# logi-cmos-7725-7670-NoFFC.net
KiCad netlist of a schematic drawn in Altium Designer
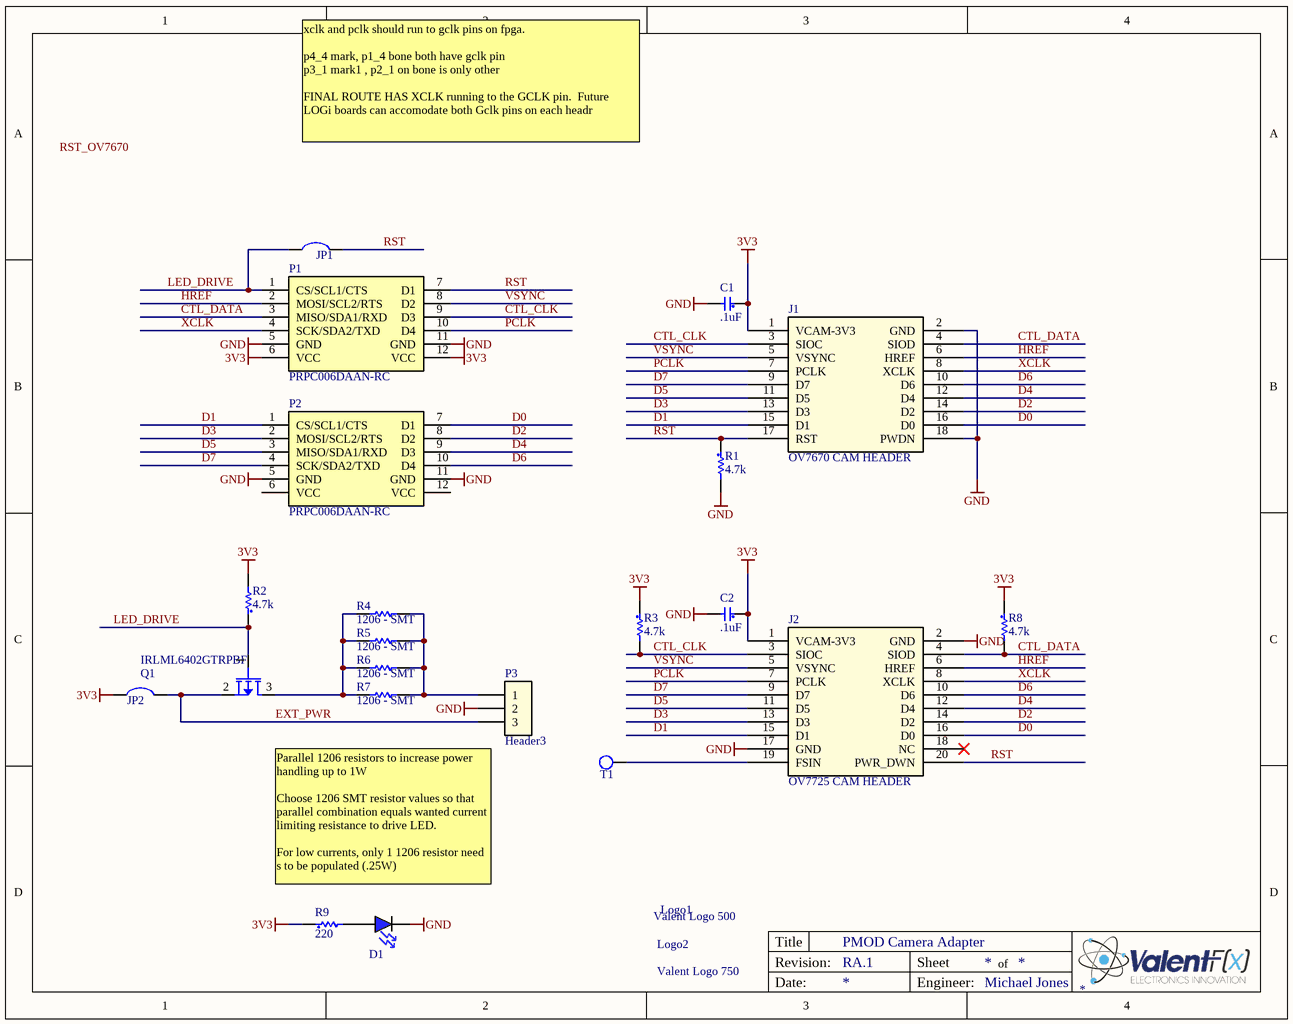
[diagram p0: logi-cmos-7725-7670-NoFFC.SchDoc]

(export (version "E")
  (design (tool "Eeschema 10.0.6"))
  (components
    (comp (ref "C1")
      (value ".1uF")
      (footprint "mRCL:C0603")
      (description ".10uF X7R 20% (MLCC) - SMD/SMT 0603 25volts")
      (fields (field (name "MANUFACTURER") "TDK") (field (name "MANUFACTURER PART NUMBER") "C1608X7R1E104MT"))
      (libsource (lib "mCapacitors") (part "C0603 - C1608X7R1E104MT"))
    )
    (comp (ref "C2")
      (value ".1uF")
      (footprint "mRCL:C0603")
      (description ".10uF X7R 20% (MLCC) - SMD/SMT 0603 25volts")
      (fields (field (name "MANUFACTURER") "TDK") (field (name "MANUFACTURER PART NUMBER") "C1608X7R1E104MT"))
      (libsource (lib "mCapacitors") (part "C0603 - C1608X7R1E104MT"))
    )
    (comp (ref "D1")
      (value "BLUE LED0603")
      (footprint "LED_0603 - BLUE")
      (description "BLUE Standard LED - SMD Blue 470nm 40mcd 20mA")
      (fields
        (field (name "MANUFACTURER") "Harvatek International")
        (field (name "MANUFACTURER PART NUMBER") "HT-193NB-5589")
      )
      (libsource (lib "mDiode") (part "LED0603 - HT-193NB-5589"))
    )
    (comp (ref "J1")
      (value "OV7670 CAM HEADER")
      (footprint "HEADER_9x2_40_100 1-3-5 THRU DIP")
      (description "CMOS CAMERA HEADER")
      (fields
        (field (name "MANUFACTURER") "Sullins Connector Solutions")
        (field (name "MANUFACTURER PART NUMBER") "PPPC092LFBN-RC")
      )
      (libsource (lib "mModule") (part "CAM - OV7670"))
    )
    (comp (ref "J2")
      (value "OV7725 CAM HEADER")
      (footprint "HEADER_10x2_40_100 1-3-5 THRU DIP")
      (description "CMOS CAMERA HEADER")
      (fields
        (field (name "MANUFACTURER") "Sullins Connector Solutions")
        (field (name "MANUFACTURER PART NUMBER") "SFH11-PBPC-D10-ST-BK")
      )
      (libsource (lib "mModule") (part "CAM - 0V7725"))
    )
    (comp (ref "JP1")
      (value "Solder Jumper")
      (footprint "SOLDER_JUMPER")
      (description "Solder/Configuration Jumper")
      (fields (field (name "MANUFACTURER") "n/a"))
      (libsource (lib "mConnector") (part "Solder Jumper"))
    )
    (comp (ref "JP2")
      (value "Solder Jumper")
      (footprint "SOLDER_JUMPER")
      (description "Solder/Configuration Jumper")
      (fields (field (name "MANUFACTURER") "n/a"))
      (libsource (lib "mConnector") (part "Solder Jumper"))
    )
    (comp (ref "Logo1")
      (value "Valent Logo 500")
      (footprint "VALENTFX_500-SolderMask")
      (libsource (lib "mLogos") (part "Valent Logo 500"))
    )
    (comp (ref "Logo2")
      (value "Valent Logo 750")
      (footprint "VALENTFX_750-SolderMask-BOT")
      (libsource (lib "mLogos") (part "Valent Logo 750"))
    )
    (comp (ref "P1")
      (value "PRPC006DAAN-RC")
      (footprint "mconnector:PMOD HEADER - Male")
      (fields
        (field (name "MANUFACTURER") "Samtec")
        (field (name "MANUFACTURER PART NUMBER") "MTSW-106-07-G-D-130-RA")
      )
      (libsource (lib "mConnector") (part "PRPC006DAAN-RC"))
    )
    (comp (ref "P2")
      (value "PRPC006DAAN-RC")
      (footprint "mconnector:PMOD HEADER - Male")
      (fields
        (field (name "MANUFACTURER") "Samtec")
        (field (name "MANUFACTURER PART NUMBER") "MTSW-106-07-G-D-130-RA")
      )
      (libsource (lib "mConnector") (part "PRPC006DAAN-RC"))
    )
    (comp (ref "P3")
      (value "Header3")
      (footprint "HEADER_3_40_100 THRU SIP")
      (description "Header  pin")
      (libsource (lib "mConnector") (part "Header3"))
    )
    (comp (ref "Q1")
      (value "IRLML6402GTRPBF")
      (footprint "SOT-23")
      (description "MOSFET P-CH 20V 3.7A SOT-23-3")
      (fields (field (name "MANUFACTURER") "International Rectifier"))
      (libsource (lib "mTransistor") (part "PMOS - IRLML6402GTRPBF"))
    )
    (comp (ref "R1")
      (value "4.7k")
      (footprint "mRCL:R0603")
      (description "4.7k Thick Film Resistors - SMD 1/10watt 4.7Kohms 1%")
      (fields
        (field (name "MANUFACTURER") "Vishay Dale")
        (field (name "MANUFACTURER PART NUMBER") "CRCW06034K70FKEA")
      )
      (libsource (lib "mResistors") (part "R0603 - CRCW06034K70FKEA"))
    )
    (comp (ref "R2")
      (value "4.7k")
      (footprint "mRCL:R0603")
      (description "4.7k Thick Film Resistors - SMD 1/10watt 4.7Kohms 1%")
      (fields
        (field (name "MANUFACTURER") "Vishay Dale")
        (field (name "MANUFACTURER PART NUMBER") "CRCW06034K70FKEA")
      )
      (libsource (lib "mResistors") (part "R0603 - CRCW06034K70FKEA"))
    )
    (comp (ref "R3")
      (value "4.7k")
      (footprint "mRCL:R0603")
      (description "4.7k Thick Film Resistors - SMD 1/10watt 4.7Kohms 1%")
      (fields
        (field (name "MANUFACTURER") "Vishay Dale")
        (field (name "MANUFACTURER PART NUMBER") "CRCW06034K70FKEA")
      )
      (libsource (lib "mResistors") (part "R0603 - CRCW06034K70FKEA"))
    )
    (comp (ref "R4")
      (value "1206 - SMT")
      (footprint "R1206")
      (description "RES 270 OHM 1/4W 5% 1206 SMD")
      (fields
        (field (name "MANUFACTURER") "Panasonic - ECG")
        (field (name "MANUFACTURER PART NUMBER") "ERJ-8GEYJ271V")
      )
      (libsource (lib "eResistors") (part "ERJ-8GEYJ271V"))
    )
    (comp (ref "R5")
      (value "1206 - SMT")
      (footprint "R1206")
      (description "RES 270 OHM 1/4W 5% 1206 SMD")
      (fields
        (field (name "MANUFACTURER") "Panasonic - ECG")
        (field (name "MANUFACTURER PART NUMBER") "ERJ-8GEYJ271V")
      )
      (libsource (lib "eResistors") (part "ERJ-8GEYJ271V"))
    )
    (comp (ref "R6")
      (value "1206 - SMT")
      (footprint "R1206")
      (description "RES 270 OHM 1/4W 5% 1206 SMD")
      (fields
        (field (name "MANUFACTURER") "Panasonic - ECG")
        (field (name "MANUFACTURER PART NUMBER") "ERJ-8GEYJ271V")
      )
      (libsource (lib "eResistors") (part "ERJ-8GEYJ271V"))
    )
    (comp (ref "R7")
      (value "1206 - SMT")
      (footprint "R1206")
      (description "RES 270 OHM 1/4W 5% 1206 SMD")
      (fields
        (field (name "MANUFACTURER") "Panasonic - ECG")
        (field (name "MANUFACTURER PART NUMBER") "ERJ-8GEYJ271V")
      )
      (libsource (lib "eResistors") (part "ERJ-8GEYJ271V"))
    )
    (comp (ref "R8")
      (value "4.7k")
      (footprint "mRCL:R0603")
      (description "4.7k Thick Film Resistors - SMD 1/10watt 4.7Kohms 1%")
      (fields
        (field (name "MANUFACTURER") "Vishay Dale")
        (field (name "MANUFACTURER PART NUMBER") "CRCW06034K70FKEA")
      )
      (libsource (lib "mResistors") (part "R0603 - CRCW06034K70FKEA"))
    )
    (comp (ref "R9")
      (value "220")
      (footprint "mRCL:R0603")
      (description "220 - thick Film Resistors - SMD 0603 220ohms 1% Tol")
      (fields
        (field (name "MANUFACTURER") "Panasonic - ECG")
        (field (name "MANUFACTURER PART NUMBER") "ERJ-3EKF2200V")
      )
      (libsource (lib "mResistors") (part "R0603 - ERJ-3EKF2200V"))
    )
    (comp (ref "T1")
      (value "Test Point")
      (footprint "Tp 25-40")
      (description "Test Point Smaller Symbol")
      (libsource (lib "mConnector") (part "Test Point 2"))
    )
  )
  (nets
    (net (code "1") (name "/CTL_CLK") (class "Default")
      (node (ref "J1") (pin "3") (pinfunction "SIOC_3") (pintype "passive"))
      (node (ref "J2") (pin "3") (pinfunction "SIOC_3") (pintype "passive"))
      (node (ref "P1") (pin "9") (pinfunction "D3_9") (pintype "power_in"))
      (node (ref "R3") (pin "2") (pinfunction "2_2") (pintype "passive"))
    )
    (net (code "2") (name "/CTL_DATA") (class "Default")
      (node (ref "J1") (pin "4") (pinfunction "SIOD_4") (pintype "passive"))
      (node (ref "J2") (pin "4") (pinfunction "SIOD_4") (pintype "passive"))
      (node (ref "P1") (pin "3") (pinfunction "MISO/SDA1/RXD_3") (pintype "power_in"))
      (node (ref "R8") (pin "2") (pinfunction "2_2") (pintype "passive"))
    )
    (net (code "3") (name "/D0") (class "Default")
      (node (ref "J1") (pin "16") (pinfunction "D0_16") (pintype "passive"))
      (node (ref "J2") (pin "16") (pinfunction "D0_16") (pintype "passive"))
      (node (ref "P2") (pin "7") (pinfunction "D1_7") (pintype "power_in"))
    )
    (net (code "4") (name "/D1") (class "Default")
      (node (ref "J1") (pin "15") (pinfunction "D1_15") (pintype "passive"))
      (node (ref "J2") (pin "15") (pinfunction "D1_15") (pintype "passive"))
      (node (ref "P2") (pin "1") (pinfunction "CS/SCL1/CTS_1") (pintype "power_in"))
    )
    (net (code "5") (name "/D2") (class "Default")
      (node (ref "J1") (pin "14") (pinfunction "D2_14") (pintype "passive"))
      (node (ref "J2") (pin "14") (pinfunction "D2_14") (pintype "passive"))
      (node (ref "P2") (pin "8") (pinfunction "D2_8") (pintype "power_in"))
    )
    (net (code "6") (name "/D3") (class "Default")
      (node (ref "J1") (pin "13") (pinfunction "D3_13") (pintype "passive"))
      (node (ref "J2") (pin "13") (pinfunction "D3_13") (pintype "passive"))
      (node (ref "P2") (pin "2") (pinfunction "MOSI/SCL2/RTS_2") (pintype "power_in"))
    )
    (net (code "7") (name "/D4") (class "Default")
      (node (ref "J1") (pin "12") (pinfunction "D4_12") (pintype "passive"))
      (node (ref "J2") (pin "12") (pinfunction "D4_12") (pintype "passive"))
      (node (ref "P2") (pin "9") (pinfunction "D3_9") (pintype "power_in"))
    )
    (net (code "8") (name "/D5") (class "Default")
      (node (ref "J1") (pin "11") (pinfunction "D5_11") (pintype "passive"))
      (node (ref "J2") (pin "11") (pinfunction "D5_11") (pintype "passive"))
      (node (ref "P2") (pin "3") (pinfunction "MISO/SDA1/RXD_3") (pintype "power_in"))
    )
    (net (code "9") (name "/D6") (class "Default")
      (node (ref "J1") (pin "10") (pinfunction "D6_10") (pintype "passive"))
      (node (ref "J2") (pin "10") (pinfunction "D6_10") (pintype "passive"))
      (node (ref "P2") (pin "10") (pinfunction "D4_10") (pintype "power_in"))
    )
    (net (code "10") (name "/D7") (class "Default")
      (node (ref "J1") (pin "9") (pinfunction "D7_9") (pintype "passive"))
      (node (ref "J2") (pin "9") (pinfunction "D7_9") (pintype "passive"))
      (node (ref "P2") (pin "4") (pinfunction "SCK/SDA2/TXD_4") (pintype "power_in"))
    )
    (net (code "11") (name "/EXT_PWR") (class "Default")
      (node (ref "JP2") (pin "2") (pinfunction "2_2") (pintype "passive"))
      (node (ref "P3") (pin "3") (pinfunction "3_3") (pintype "passive"))
      (node (ref "Q1") (pin "2") (pinfunction "S_2") (pintype "passive"))
    )
    (net (code "12") (name "/HREF") (class "Default")
      (node (ref "J1") (pin "6") (pinfunction "HREF_6") (pintype "passive"))
      (node (ref "J2") (pin "6") (pinfunction "HREF_6") (pintype "passive"))
      (node (ref "P1") (pin "2") (pinfunction "MOSI/SCL2/RTS_2") (pintype "power_in"))
    )
    (net (code "13") (name "/LED_DRIVE") (class "Default")
      (node (ref "JP1") (pin "1") (pinfunction "1_1") (pintype "passive"))
      (node (ref "P1") (pin "1") (pinfunction "CS/SCL1/CTS_1") (pintype "power_in"))
      (node (ref "Q1") (pin "1") (pinfunction "G_1") (pintype "passive"))
      (node (ref "R2") (pin "1") (pinfunction "1_1") (pintype "passive"))
    )
    (net (code "14") (name "/PCLK") (class "Default")
      (node (ref "J1") (pin "7") (pinfunction "PCLK_7") (pintype "passive"))
      (node (ref "J2") (pin "7") (pinfunction "PCLK_7") (pintype "passive"))
      (node (ref "P1") (pin "10") (pinfunction "D4_10") (pintype "power_in"))
    )
    (net (code "15") (name "/RST") (class "Default")
      (node (ref "J1") (pin "17") (pinfunction "RST_17") (pintype "passive"))
      (node (ref "J2") (pin "20") (pinfunction "PWR_DWN_20") (pintype "passive"))
      (node (ref "JP1") (pin "2") (pinfunction "2_2") (pintype "passive"))
      (node (ref "P1") (pin "7") (pinfunction "D1_7") (pintype "power_in"))
      (node (ref "R1") (pin "1") (pinfunction "1_1") (pintype "passive"))
    )
    (net (code "17") (name "/VSYNC") (class "Default")
      (node (ref "J1") (pin "5") (pinfunction "VSYNC_5") (pintype "passive"))
      (node (ref "J2") (pin "5") (pinfunction "VSYNC_5") (pintype "passive"))
      (node (ref "P1") (pin "8") (pinfunction "D2_8") (pintype "power_in"))
    )
    (net (code "18") (name "/XCLK") (class "Default")
      (node (ref "J1") (pin "8") (pinfunction "XCLK_8") (pintype "passive"))
      (node (ref "J2") (pin "8") (pinfunction "XCLK_8") (pintype "passive"))
      (node (ref "P1") (pin "4") (pinfunction "SCK/SDA2/TXD_4") (pintype "power_in"))
    )
    (net (code "19") (name "3V3") (class "Default")
      (node (ref "C1") (pin "1") (pinfunction "1_1") (pintype "passive"))
      (node (ref "C2") (pin "1") (pinfunction "1_1") (pintype "passive"))
      (node (ref "J1") (pin "1") (pinfunction "VCAM-3V3_1") (pintype "passive"))
      (node (ref "J2") (pin "1") (pinfunction "VCAM-3V3_1") (pintype "passive"))
      (node (ref "JP2") (pin "1") (pinfunction "1_1") (pintype "passive"))
      (node (ref "P1") (pin "12") (pinfunction "VCC_12") (pintype "power_in"))
      (node (ref "P1") (pin "6") (pinfunction "VCC_6") (pintype "power_in"))
      (node (ref "R2") (pin "2") (pinfunction "2_2") (pintype "passive"))
      (node (ref "R3") (pin "1") (pinfunction "1_1") (pintype "passive"))
      (node (ref "R8") (pin "1") (pinfunction "1_1") (pintype "passive"))
      (node (ref "R9") (pin "1") (pinfunction "1_1") (pintype "passive"))
    )
    (net (code "20") (name "GND") (class "Default")
      (node (ref "C1") (pin "2") (pinfunction "2_2") (pintype "passive"))
      (node (ref "C2") (pin "2") (pinfunction "2_2") (pintype "passive"))
      (node (ref "D1") (pin "C") (pinfunction "C_C") (pintype "passive"))
      (node (ref "J1") (pin "18") (pinfunction "PWDN_18") (pintype "passive"))
      (node (ref "J1") (pin "2") (pinfunction "GND_2") (pintype "passive"))
      (node (ref "J2") (pin "17") (pinfunction "GND_17") (pintype "passive"))
      (node (ref "J2") (pin "2") (pinfunction "GND_2") (pintype "passive"))
      (node (ref "P1") (pin "11") (pinfunction "GND_11") (pintype "power_in"))
      (node (ref "P1") (pin "5") (pinfunction "GND_5") (pintype "power_in"))
      (node (ref "P2") (pin "11") (pinfunction "GND_11") (pintype "power_in"))
      (node (ref "P2") (pin "5") (pinfunction "GND_5") (pintype "power_in"))
      (node (ref "P3") (pin "2") (pinfunction "2_2") (pintype "passive"))
      (node (ref "R1") (pin "2") (pinfunction "2_2") (pintype "passive"))
    )
    (net (code "21") (name "Net-(D1-PadA)") (class "Default")
      (node (ref "D1") (pin "A") (pinfunction "A_A") (pintype "passive"))
      (node (ref "R9") (pin "2") (pinfunction "2_2") (pintype "passive"))
    )
    (net (code "22") (name "Net-(J2-FSIN)") (class "Default")
      (node (ref "J2") (pin "19") (pinfunction "FSIN_19") (pintype "passive"))
      (node (ref "T1") (pin "1") (pinfunction "1_1") (pintype "passive"))
    )
    (net (code "23") (name "Net-(P3-Pad1)") (class "Default")
      (node (ref "P3") (pin "1") (pinfunction "1_1") (pintype "passive"))
      (node (ref "R4") (pin "2") (pinfunction "2_2") (pintype "passive"))
      (node (ref "R5") (pin "2") (pinfunction "2_2") (pintype "passive"))
      (node (ref "R6") (pin "2") (pinfunction "2_2") (pintype "passive"))
      (node (ref "R7") (pin "2") (pinfunction "2_2") (pintype "passive"))
    )
    (net (code "24") (name "Net-(Q1-D)") (class "Default")
      (node (ref "Q1") (pin "3") (pinfunction "D_3") (pintype "passive"))
      (node (ref "R4") (pin "1") (pinfunction "1_1") (pintype "passive"))
      (node (ref "R5") (pin "1") (pinfunction "1_1") (pintype "passive"))
      (node (ref "R6") (pin "1") (pinfunction "1_1") (pintype "passive"))
      (node (ref "R7") (pin "1") (pinfunction "1_1") (pintype "passive"))
    )
    (net (code "25") (name "unconnected-(J2-NC-Pad18)") (class "Default")
      (node (ref "J2") (pin "18") (pinfunction "NC_18") (pintype "passive+no_connect"))
    )
    (net (code "26") (name "unconnected-(P2-VCC-Pad6)") (class "Default")
      (node (ref "P2") (pin "6") (pinfunction "VCC_6") (pintype "power_in"))
    )
    (net (code "27") (name "unconnected-(P2-VCC-Pad12)") (class "Default")
      (node (ref "P2") (pin "12") (pinfunction "VCC_12") (pintype "power_in"))
    )
  )
)
